# 780-00021_rev1_pg1_3-Chan_IR_Thermocoupl.net
KiCad netlist of a schematic drawn in Altium Designer
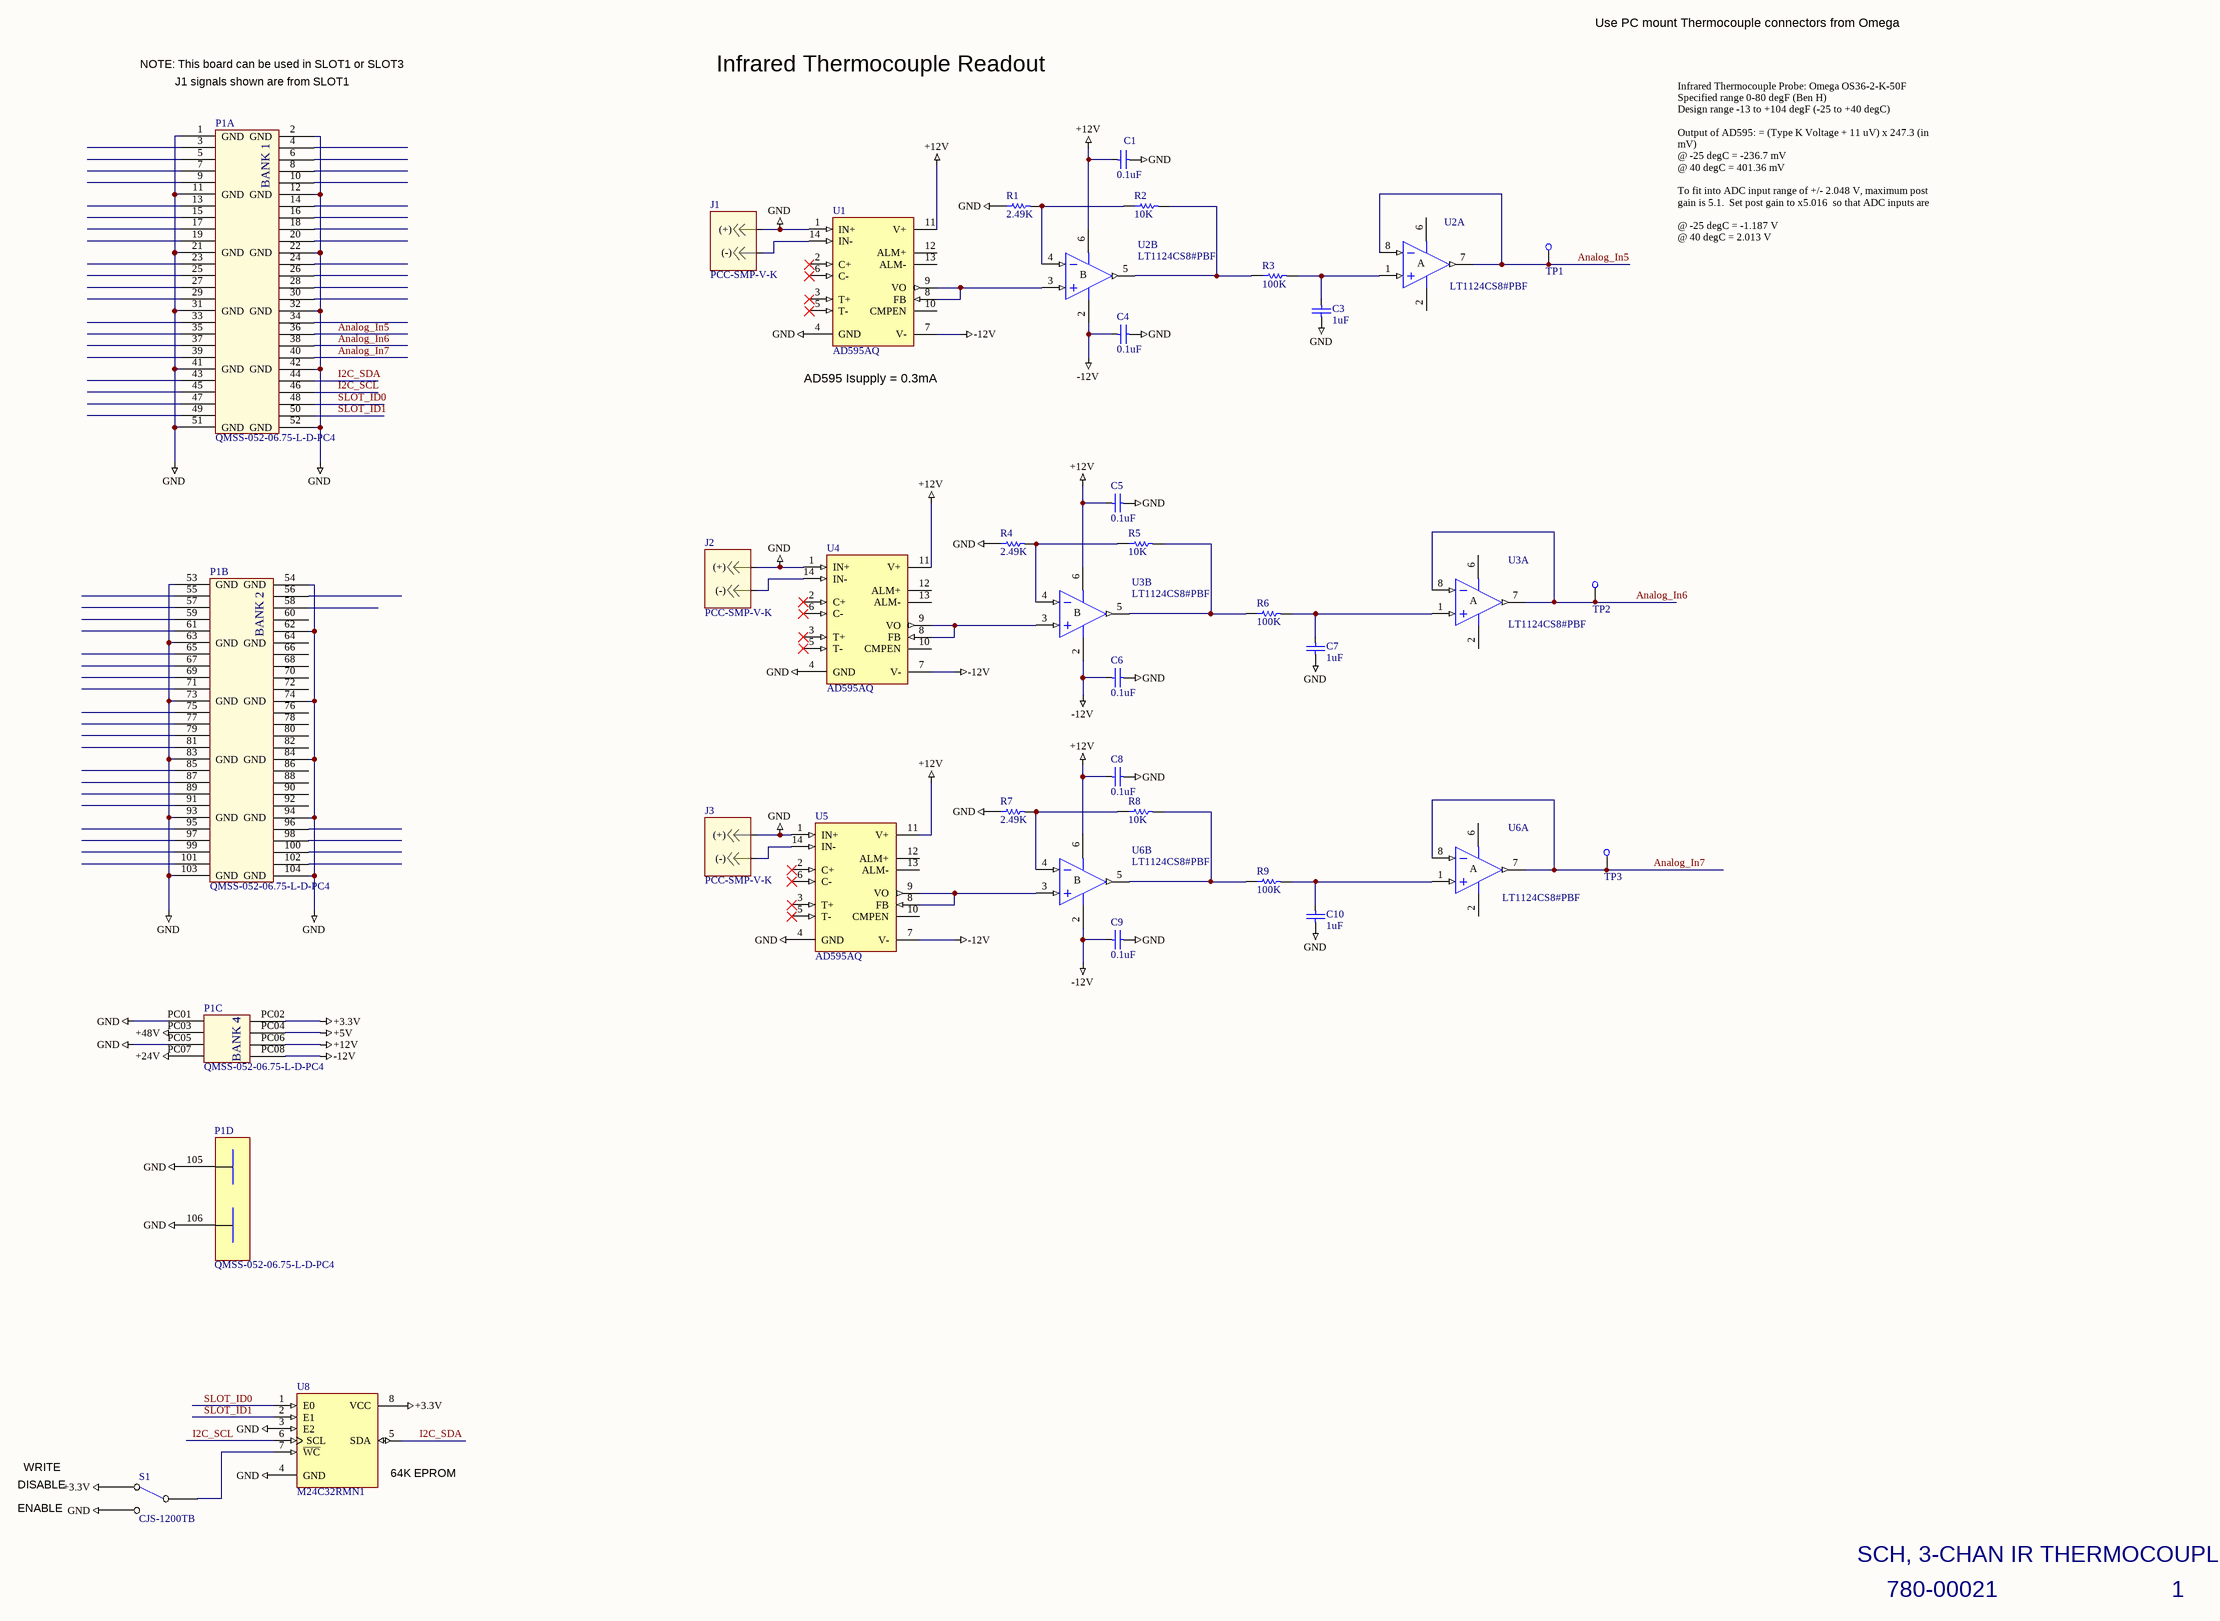
[diagram p0: 780-00021_rev1,pg1,3-Chan IR Thermocouple Apps Module.SchDoc]

(export (version "E")
  (design (tool "Eeschema 10.0.6"))
  (components
    (comp (ref "C1")
      (value "0.1uF")
      (footprint "SMD_0805")
      (description "Capacitor")
      (fields (field (name "Comment") "Cap SMD"))
      (libsource (lib "Richs Schematic Components") (part "Cap SMD"))
    )
    (comp (ref "C3")
      (value "1uF")
      (footprint "SMD_0805")
      (description "Capacitor")
      (fields (field (name "Comment") "Cap SMD"))
      (libsource (lib "Richs Schematic Components") (part "Cap SMD"))
    )
    (comp (ref "C4")
      (value "0.1uF")
      (footprint "SMD_0805")
      (description "Capacitor")
      (fields (field (name "Comment") "Cap SMD"))
      (libsource (lib "Richs Schematic Components") (part "Cap SMD"))
    )
    (comp (ref "C5")
      (value "0.1uF")
      (footprint "SMD_0805")
      (description "Capacitor")
      (fields (field (name "Comment") "Cap SMD"))
      (libsource (lib "Richs Schematic Components") (part "Cap SMD"))
    )
    (comp (ref "C6")
      (value "0.1uF")
      (footprint "SMD_0805")
      (description "Capacitor")
      (fields (field (name "Comment") "Cap SMD"))
      (libsource (lib "Richs Schematic Components") (part "Cap SMD"))
    )
    (comp (ref "C7")
      (value "1uF")
      (footprint "SMD_0805")
      (description "Capacitor")
      (fields (field (name "Comment") "Cap SMD"))
      (libsource (lib "Richs Schematic Components") (part "Cap SMD"))
    )
    (comp (ref "C8")
      (value "0.1uF")
      (footprint "SMD_0805")
      (description "Capacitor")
      (fields (field (name "Comment") "Cap SMD"))
      (libsource (lib "Richs Schematic Components") (part "Cap SMD"))
    )
    (comp (ref "C9")
      (value "0.1uF")
      (footprint "SMD_0805")
      (description "Capacitor")
      (fields (field (name "Comment") "Cap SMD"))
      (libsource (lib "Richs Schematic Components") (part "Cap SMD"))
    )
    (comp (ref "C10")
      (value "1uF")
      (footprint "SMD_0805")
      (description "Capacitor")
      (fields (field (name "Comment") "Cap SMD"))
      (libsource (lib "Richs Schematic Components") (part "Cap SMD"))
    )
    (comp (ref "J1")
      (value "PCC-SMP-V-K")
      (footprint "THERMOCOUPLE, Vertical")
      (description "T/C Conn PCB mount vertical")
      (libsource (lib "Richs Schematic Components") (part "Thermocouple Connector"))
    )
    (comp (ref "J2")
      (value "PCC-SMP-V-K")
      (footprint "THERMOCOUPLE, Vertical")
      (description "T/C Conn PCB mount vertical")
      (libsource (lib "Richs Schematic Components") (part "Thermocouple Connector"))
    )
    (comp (ref "J3")
      (value "PCC-SMP-V-K")
      (footprint "THERMOCOUPLE, Vertical")
      (description "T/C Conn PCB mount vertical")
      (libsource (lib "Richs Schematic Components") (part "Thermocouple Connector"))
    )
    (comp (ref "P1")
      (value "QMSS-052-06.75-L-D-PC4")
      (footprint "QMS SMD PWR PINS - 104PIN")
      (description "SAMTEC QMSS W/PWR PINS")
      (fields (field (name "MANUFACTURER") "SAMTEC"))
      (libsource (lib "Richs Schematic Components") (part "QMSS-PC4-104 pin"))
    )
    (comp (ref "R1")
      (value "2.49K")
      (footprint "SMD_0805")
      (description "Resistor 0805")
      (fields (field (name "MANUFACTURER") "Vishay/Dale") (field (name "Comment") "Res 0805"))
      (libsource (lib "Richs Schematic Components") (part "Res SMD"))
    )
    (comp (ref "R2")
      (value "10K")
      (footprint "SMD_0805")
      (description "Resistor 0805")
      (fields (field (name "MANUFACTURER") "Vishay/Dale") (field (name "Comment") "Res 0805"))
      (libsource (lib "Richs Schematic Components") (part "Res SMD"))
    )
    (comp (ref "R3")
      (value "100K")
      (footprint "SMD_0805")
      (description "Resistor 0805")
      (fields (field (name "MANUFACTURER") "Vishay/Dale") (field (name "Comment") "Res 0805"))
      (libsource (lib "Richs Schematic Components") (part "Res SMD"))
    )
    (comp (ref "R4")
      (value "2.49K")
      (footprint "SMD_0805")
      (description "Resistor 0805")
      (fields (field (name "MANUFACTURER") "Vishay/Dale") (field (name "Comment") "Res 0805"))
      (libsource (lib "Richs Schematic Components") (part "Res SMD"))
    )
    (comp (ref "R5")
      (value "10K")
      (footprint "SMD_0805")
      (description "Resistor 0805")
      (fields (field (name "MANUFACTURER") "Vishay/Dale") (field (name "Comment") "Res 0805"))
      (libsource (lib "Richs Schematic Components") (part "Res SMD"))
    )
    (comp (ref "R6")
      (value "100K")
      (footprint "SMD_0805")
      (description "Resistor 0805")
      (fields (field (name "MANUFACTURER") "Vishay/Dale") (field (name "Comment") "Res 0805"))
      (libsource (lib "Richs Schematic Components") (part "Res SMD"))
    )
    (comp (ref "R7")
      (value "2.49K")
      (footprint "SMD_0805")
      (description "Resistor 0805")
      (fields (field (name "MANUFACTURER") "Vishay/Dale") (field (name "Comment") "Res 0805"))
      (libsource (lib "Richs Schematic Components") (part "Res SMD"))
    )
    (comp (ref "R8")
      (value "10K")
      (footprint "SMD_0805")
      (description "Resistor 0805")
      (fields (field (name "MANUFACTURER") "Vishay/Dale") (field (name "Comment") "Res 0805"))
      (libsource (lib "Richs Schematic Components") (part "Res SMD"))
    )
    (comp (ref "R9")
      (value "100K")
      (footprint "SMD_0805")
      (description "Resistor 0805")
      (fields (field (name "MANUFACTURER") "Vishay/Dale") (field (name "Comment") "Res 0805"))
      (libsource (lib "Richs Schematic Components") (part "Res SMD"))
    )
    (comp (ref "S1")
      (value "CJS-1200TB")
      (footprint "CAS-120B")
      (fields (field (name "MANUFACTURER") "Copal Electronics"))
      (libsource (lib "JON_1_Library") (part "SW_SPDT_DOUG"))
    )
    (comp (ref "TP1")
      (value "Test Point SMD")
      (footprint "SMD_TEST POINT")
      (description "SMD loop test point")
      (libsource (lib "Richs Schematic Components") (part "Test Point SMD"))
    )
    (comp (ref "TP2")
      (value "Test Point SMD")
      (footprint "SMD_TEST POINT")
      (description "SMD loop test point")
      (libsource (lib "Richs Schematic Components") (part "Test Point SMD"))
    )
    (comp (ref "TP3")
      (value "Test Point SMD")
      (footprint "SMD_TEST POINT")
      (description "SMD loop test point")
      (libsource (lib "Richs Schematic Components") (part "Test Point SMD"))
    )
    (comp (ref "U1")
      (value "AD595AQ")
      (footprint "Q-14_A")
      (description "Monolithic Thermocouple Amplifier with Cold Junction Compensation")
      (fields (field (name "MANUFACTURER") "Analog Devices"))
      (libsource (lib "AD Thermocouple Amplifier") (part "AD595AQ"))
    )
    (comp (ref "U2")
      (value "LT1124CS8#PBF")
      (footprint "S8_N")
      (description "Dual Low Noise, High-Speed Precision Operational Amplifier")
      (libsource (lib "LT Operational Amplifier") (part "LT1124CS8#PBF"))
    )
    (comp (ref "U3")
      (value "LT1124CS8#PBF")
      (footprint "S8_N")
      (description "Dual Low Noise, High-Speed Precision Operational Amplifier")
      (libsource (lib "LT Operational Amplifier") (part "LT1124CS8#PBF"))
    )
    (comp (ref "U4")
      (value "AD595AQ")
      (footprint "Q-14_A")
      (description "Monolithic Thermocouple Amplifier with Cold Junction Compensation")
      (fields (field (name "MANUFACTURER") "Analog Devices"))
      (libsource (lib "AD Thermocouple Amplifier") (part "AD595AQ"))
    )
    (comp (ref "U5")
      (value "AD595AQ")
      (footprint "Q-14_A")
      (description "Monolithic Thermocouple Amplifier with Cold Junction Compensation")
      (fields (field (name "MANUFACTURER") "Analog Devices"))
      (libsource (lib "AD Thermocouple Amplifier") (part "AD595AQ"))
    )
    (comp (ref "U6")
      (value "LT1124CS8#PBF")
      (footprint "S8_N")
      (description "Dual Low Noise, High-Speed Precision Operational Amplifier")
      (libsource (lib "LT Operational Amplifier") (part "LT1124CS8#PBF"))
    )
    (comp (ref "U8")
      (value "M24C32RMN1")
      (footprint "SOP8_N")
      (description "32 Kbit Serial I²C Bus EEPROM")
      (libsource (lib "ST Memory EEPROM Serial") (part "M24C32RMN1"))
    )
  )
  (nets
    (net (code "1") (name "+3.3V") (class "Default")
      (node (ref "P1") (pin "PC02") (pinfunction "PC02_PC02") (pintype "passive"))
      (node (ref "S1") (pin "3") (pinfunction "NC_3") (pintype "passive"))
      (node (ref "U8") (pin "8") (pinfunction "VCC_8") (pintype "power_in"))
    )
    (net (code "2") (name "+5V") (class "Default")
      (node (ref "P1") (pin "PC04") (pinfunction "PC04_PC04") (pintype "passive"))
    )
    (net (code "3") (name "+12V") (class "Default")
      (node (ref "C1") (pin "2") (pinfunction "2_2") (pintype "passive"))
      (node (ref "C5") (pin "2") (pinfunction "2_2") (pintype "passive"))
      (node (ref "C8") (pin "2") (pinfunction "2_2") (pintype "passive"))
      (node (ref "P1") (pin "PC06") (pinfunction "PC06_PC06") (pintype "passive"))
      (node (ref "U1") (pin "11") (pinfunction "V+_11") (pintype "power_in"))
      (node (ref "U2") (pin "6") (pinfunction "V+_6") (pintype "power_in"))
      (node (ref "U3") (pin "6") (pinfunction "V+_6") (pintype "power_in"))
      (node (ref "U4") (pin "11") (pinfunction "V+_11") (pintype "power_in"))
      (node (ref "U5") (pin "11") (pinfunction "V+_11") (pintype "power_in"))
      (node (ref "U6") (pin "6") (pinfunction "V+_6") (pintype "power_in"))
    )
    (net (code "6") (name "-12V") (class "Default")
      (node (ref "C4") (pin "2") (pinfunction "2_2") (pintype "passive"))
      (node (ref "C6") (pin "2") (pinfunction "2_2") (pintype "passive"))
      (node (ref "C9") (pin "2") (pinfunction "2_2") (pintype "passive"))
      (node (ref "P1") (pin "PC08") (pinfunction "PC08_PC08") (pintype "passive"))
      (node (ref "U1") (pin "7") (pinfunction "V-_7") (pintype "power_in"))
      (node (ref "U2") (pin "2") (pinfunction "V-_2") (pintype "power_in"))
      (node (ref "U3") (pin "2") (pinfunction "V-_2") (pintype "power_in"))
      (node (ref "U4") (pin "7") (pinfunction "V-_7") (pintype "power_in"))
      (node (ref "U5") (pin "7") (pinfunction "V-_7") (pintype "power_in"))
      (node (ref "U6") (pin "2") (pinfunction "V-_2") (pintype "power_in"))
    )
    (net (code "7") (name "/Analog_In5") (class "Default")
      (node (ref "P1") (pin "36") (pinfunction "36_36") (pintype "passive"))
      (node (ref "TP1") (pin "1") (pinfunction "TP_1") (pintype "passive"))
      (node (ref "U2") (pin "7") (pinfunction "OUT_7") (pintype "output"))
      (node (ref "U2") (pin "8") (pinfunction "IN-_8") (pintype "input"))
    )
    (net (code "8") (name "/Analog_In6") (class "Default")
      (node (ref "P1") (pin "38") (pinfunction "38_38") (pintype "passive"))
      (node (ref "TP2") (pin "1") (pinfunction "TP_1") (pintype "passive"))
      (node (ref "U3") (pin "7") (pinfunction "OUT_7") (pintype "output"))
      (node (ref "U3") (pin "8") (pinfunction "IN-_8") (pintype "input"))
    )
    (net (code "9") (name "/Analog_In7") (class "Default")
      (node (ref "P1") (pin "40") (pinfunction "40_40") (pintype "passive"))
      (node (ref "TP3") (pin "1") (pinfunction "TP_1") (pintype "passive"))
      (node (ref "U6") (pin "7") (pinfunction "OUT_7") (pintype "output"))
      (node (ref "U6") (pin "8") (pinfunction "IN-_8") (pintype "input"))
    )
    (net (code "10") (name "/I2C_SCL") (class "Default")
      (node (ref "P1") (pin "46") (pinfunction "46_46") (pintype "passive"))
      (node (ref "U8") (pin "6") (pinfunction "SCL_6") (pintype "input"))
    )
    (net (code "11") (name "/I2C_SDA") (class "Default")
      (node (ref "P1") (pin "44") (pinfunction "44_44") (pintype "passive"))
      (node (ref "U8") (pin "5") (pinfunction "SDA_5") (pintype "bidirectional"))
    )
    (net (code "12") (name "/SLOT_ID0") (class "Default")
      (node (ref "P1") (pin "48") (pinfunction "48_48") (pintype "passive"))
      (node (ref "U8") (pin "1") (pinfunction "E0_1") (pintype "input"))
    )
    (net (code "13") (name "/SLOT_ID1") (class "Default")
      (node (ref "P1") (pin "50") (pinfunction "50_50") (pintype "passive"))
      (node (ref "U8") (pin "2") (pinfunction "E1_2") (pintype "input"))
    )
    (net (code "14") (name "GND") (class "Default")
      (node (ref "C1") (pin "1") (pinfunction "1_1") (pintype "passive"))
      (node (ref "C10") (pin "1") (pinfunction "1_1") (pintype "passive"))
      (node (ref "C3") (pin "1") (pinfunction "1_1") (pintype "passive"))
      (node (ref "C4") (pin "1") (pinfunction "1_1") (pintype "passive"))
      (node (ref "C5") (pin "1") (pinfunction "1_1") (pintype "passive"))
      (node (ref "C6") (pin "1") (pinfunction "1_1") (pintype "passive"))
      (node (ref "C7") (pin "1") (pinfunction "1_1") (pintype "passive"))
      (node (ref "C8") (pin "1") (pinfunction "1_1") (pintype "passive"))
      (node (ref "C9") (pin "1") (pinfunction "1_1") (pintype "passive"))
      (node (ref "J1") (pin "1") (pinfunction "(+)_1") (pintype "passive"))
      (node (ref "J2") (pin "1") (pinfunction "(+)_1") (pintype "passive"))
      (node (ref "J3") (pin "1") (pinfunction "(+)_1") (pintype "passive"))
      (node (ref "P1") (pin "1") (pinfunction "GND_1") (pintype "passive"))
      (node (ref "P1") (pin "103") (pinfunction "GND_103") (pintype "passive"))
      (node (ref "P1") (pin "104") (pinfunction "GND_104") (pintype "passive"))
      (node (ref "P1") (pin "105") (pinfunction "GND_105") (pintype "passive"))
      (node (ref "P1") (pin "106") (pinfunction "GND_106") (pintype "passive"))
      (node (ref "P1") (pin "11") (pinfunction "GND_11") (pintype "passive"))
      (node (ref "P1") (pin "12") (pinfunction "GND_12") (pintype "passive"))
      (node (ref "P1") (pin "2") (pinfunction "GND_2") (pintype "passive"))
      (node (ref "P1") (pin "21") (pinfunction "GND_21") (pintype "passive"))
      (node (ref "P1") (pin "22") (pinfunction "GND_22") (pintype "passive"))
      (node (ref "P1") (pin "31") (pinfunction "GND_31") (pintype "passive"))
      (node (ref "P1") (pin "32") (pinfunction "GND_32") (pintype "passive"))
      (node (ref "P1") (pin "41") (pinfunction "GND_41") (pintype "passive"))
      (node (ref "P1") (pin "42") (pinfunction "GND_42") (pintype "passive"))
      (node (ref "P1") (pin "51") (pinfunction "GND_51") (pintype "passive"))
      (node (ref "P1") (pin "52") (pinfunction "GND_52") (pintype "passive"))
      (node (ref "P1") (pin "53") (pinfunction "GND_53") (pintype "passive"))
      (node (ref "P1") (pin "54") (pinfunction "GND_54") (pintype "passive"))
      (node (ref "P1") (pin "62") (pinfunction "62_62") (pintype "passive"))
      (node (ref "P1") (pin "63") (pinfunction "GND_63") (pintype "passive"))
      (node (ref "P1") (pin "73") (pinfunction "GND_73") (pintype "passive"))
      (node (ref "P1") (pin "74") (pinfunction "GND_74") (pintype "passive"))
      (node (ref "P1") (pin "83") (pinfunction "GND_83") (pintype "passive"))
      (node (ref "P1") (pin "84") (pinfunction "GND_84") (pintype "passive"))
      (node (ref "P1") (pin "93") (pinfunction "GND_93") (pintype "passive"))
      (node (ref "P1") (pin "94") (pinfunction "GND_94") (pintype "passive"))
      (node (ref "P1") (pin "PC01") (pinfunction "PC01_PC01") (pintype "passive"))
      (node (ref "P1") (pin "PC05") (pinfunction "PC05_PC05") (pintype "passive"))
      (node (ref "R1") (pin "1") (pinfunction "1_1") (pintype "passive"))
      (node (ref "R4") (pin "1") (pinfunction "1_1") (pintype "passive"))
      (node (ref "R7") (pin "1") (pinfunction "1_1") (pintype "passive"))
      (node (ref "S1") (pin "1") (pinfunction "NO_1") (pintype "passive"))
      (node (ref "U1") (pin "1") (pinfunction "IN+_1") (pintype "input"))
      (node (ref "U1") (pin "4") (pinfunction "GND_4") (pintype "power_in"))
      (node (ref "U4") (pin "1") (pinfunction "IN+_1") (pintype "input"))
      (node (ref "U4") (pin "4") (pinfunction "GND_4") (pintype "power_in"))
      (node (ref "U5") (pin "1") (pinfunction "IN+_1") (pintype "input"))
      (node (ref "U5") (pin "4") (pinfunction "GND_4") (pintype "power_in"))
      (node (ref "U8") (pin "3") (pinfunction "E2_3") (pintype "input"))
      (node (ref "U8") (pin "4") (pinfunction "GND_4") (pintype "power_in"))
    )
    (net (code "15") (name "Net-(J1-(-))") (class "Default")
      (node (ref "J1") (pin "2") (pinfunction "(-)_2") (pintype "passive"))
      (node (ref "U1") (pin "14") (pinfunction "IN-_14") (pintype "input"))
    )
    (net (code "16") (name "Net-(J2-(-))") (class "Default")
      (node (ref "J2") (pin "2") (pinfunction "(-)_2") (pintype "passive"))
      (node (ref "U4") (pin "14") (pinfunction "IN-_14") (pintype "input"))
    )
    (net (code "17") (name "Net-(J3-(-))") (class "Default")
      (node (ref "J3") (pin "2") (pinfunction "(-)_2") (pintype "passive"))
      (node (ref "U5") (pin "14") (pinfunction "IN-_14") (pintype "input"))
    )
    (net (code "18") (name "Net-(S1-COM)") (class "Default")
      (node (ref "S1") (pin "2") (pinfunction "COM_2") (pintype "passive"))
      (node (ref "U8") (pin "7") (pinfunction "~{WC}_7") (pintype "input"))
    )
    (net (code "19") (name "Net-(U1-FB)") (class "Default")
      (node (ref "U1") (pin "8") (pinfunction "FB_8") (pintype "input"))
      (node (ref "U1") (pin "9") (pinfunction "VO_9") (pintype "output"))
      (node (ref "U2") (pin "3") (pinfunction "IN+_3") (pintype "input"))
    )
    (net (code "20") (name "Net-(U2A-IN+)") (class "Default")
      (node (ref "C3") (pin "2") (pinfunction "2_2") (pintype "passive"))
      (node (ref "R3") (pin "2") (pinfunction "2_2") (pintype "passive"))
      (node (ref "U2") (pin "1") (pinfunction "IN+_1") (pintype "input"))
    )
    (net (code "21") (name "Net-(U2B-IN-)") (class "Default")
      (node (ref "R1") (pin "2") (pinfunction "2_2") (pintype "passive"))
      (node (ref "R2") (pin "1") (pinfunction "1_1") (pintype "passive"))
      (node (ref "U2") (pin "4") (pinfunction "IN-_4") (pintype "input"))
    )
    (net (code "22") (name "Net-(U2B-OUT)") (class "Default")
      (node (ref "R2") (pin "2") (pinfunction "2_2") (pintype "passive"))
      (node (ref "R3") (pin "1") (pinfunction "1_1") (pintype "passive"))
      (node (ref "U2") (pin "5") (pinfunction "OUT_5") (pintype "output"))
    )
    (net (code "23") (name "Net-(U3A-IN+)") (class "Default")
      (node (ref "C7") (pin "2") (pinfunction "2_2") (pintype "passive"))
      (node (ref "R6") (pin "2") (pinfunction "2_2") (pintype "passive"))
      (node (ref "U3") (pin "1") (pinfunction "IN+_1") (pintype "input"))
    )
    (net (code "24") (name "Net-(U3B-IN+)") (class "Default")
      (node (ref "U3") (pin "3") (pinfunction "IN+_3") (pintype "input"))
      (node (ref "U4") (pin "8") (pinfunction "FB_8") (pintype "input"))
      (node (ref "U4") (pin "9") (pinfunction "VO_9") (pintype "output"))
    )
    (net (code "25") (name "Net-(U3B-IN-)") (class "Default")
      (node (ref "R4") (pin "2") (pinfunction "2_2") (pintype "passive"))
      (node (ref "R5") (pin "1") (pinfunction "1_1") (pintype "passive"))
      (node (ref "U3") (pin "4") (pinfunction "IN-_4") (pintype "input"))
    )
    (net (code "26") (name "Net-(U3B-OUT)") (class "Default")
      (node (ref "R5") (pin "2") (pinfunction "2_2") (pintype "passive"))
      (node (ref "R6") (pin "1") (pinfunction "1_1") (pintype "passive"))
      (node (ref "U3") (pin "5") (pinfunction "OUT_5") (pintype "output"))
    )
    (net (code "27") (name "Net-(U5-FB)") (class "Default")
      (node (ref "U5") (pin "8") (pinfunction "FB_8") (pintype "input"))
      (node (ref "U5") (pin "9") (pinfunction "VO_9") (pintype "output"))
      (node (ref "U6") (pin "3") (pinfunction "IN+_3") (pintype "input"))
    )
    (net (code "28") (name "Net-(U6A-IN+)") (class "Default")
      (node (ref "C10") (pin "2") (pinfunction "2_2") (pintype "passive"))
      (node (ref "R9") (pin "2") (pinfunction "2_2") (pintype "passive"))
      (node (ref "U6") (pin "1") (pinfunction "IN+_1") (pintype "input"))
    )
    (net (code "29") (name "Net-(U6B-IN-)") (class "Default")
      (node (ref "R7") (pin "2") (pinfunction "2_2") (pintype "passive"))
      (node (ref "R8") (pin "1") (pinfunction "1_1") (pintype "passive"))
      (node (ref "U6") (pin "4") (pinfunction "IN-_4") (pintype "input"))
    )
    (net (code "30") (name "Net-(U6B-OUT)") (class "Default")
      (node (ref "R8") (pin "2") (pinfunction "2_2") (pintype "passive"))
      (node (ref "R9") (pin "1") (pinfunction "1_1") (pintype "passive"))
      (node (ref "U6") (pin "5") (pinfunction "OUT_5") (pintype "output"))
    )
    (net (code "31") (name "unconnected-(P1-Pad3)") (class "Default")
      (node (ref "P1") (pin "3") (pinfunction "3_3") (pintype "passive"))
    )
    (net (code "32") (name "unconnected-(P1-Pad4)") (class "Default")
      (node (ref "P1") (pin "4") (pinfunction "4_4") (pintype "passive"))
    )
    (net (code "33") (name "unconnected-(P1-Pad5)") (class "Default")
      (node (ref "P1") (pin "5") (pinfunction "5_5") (pintype "passive"))
    )
    (net (code "34") (name "unconnected-(P1-Pad6)") (class "Default")
      (node (ref "P1") (pin "6") (pinfunction "6_6") (pintype "passive"))
    )
    (net (code "35") (name "unconnected-(P1-Pad7)") (class "Default")
      (node (ref "P1") (pin "7") (pinfunction "7_7") (pintype "passive"))
    )
    (net (code "36") (name "unconnected-(P1-Pad8)") (class "Default")
      (node (ref "P1") (pin "8") (pinfunction "8_8") (pintype "passive"))
    )
    (net (code "37") (name "unconnected-(P1-Pad9)") (class "Default")
      (node (ref "P1") (pin "9") (pinfunction "9_9") (pintype "passive"))
    )
    (net (code "38") (name "unconnected-(P1-Pad10)") (class "Default")
      (node (ref "P1") (pin "10") (pinfunction "10_10") (pintype "passive"))
    )
    (net (code "39") (name "unconnected-(P1-Pad13)") (class "Default")
      (node (ref "P1") (pin "13") (pinfunction "13_13") (pintype "passive"))
    )
    (net (code "40") (name "unconnected-(P1-Pad14)") (class "Default")
      (node (ref "P1") (pin "14") (pinfunction "14_14") (pintype "passive"))
    )
    (net (code "41") (name "unconnected-(P1-Pad15)") (class "Default")
      (node (ref "P1") (pin "15") (pinfunction "15_15") (pintype "passive"))
    )
    (net (code "42") (name "unconnected-(P1-Pad16)") (class "Default")
      (node (ref "P1") (pin "16") (pinfunction "16_16") (pintype "passive"))
    )
    (net (code "43") (name "unconnected-(P1-Pad17)") (class "Default")
      (node (ref "P1") (pin "17") (pinfunction "17_17") (pintype "passive"))
    )
    (net (code "44") (name "unconnected-(P1-Pad18)") (class "Default")
      (node (ref "P1") (pin "18") (pinfunction "18_18") (pintype "passive"))
    )
    (net (code "45") (name "unconnected-(P1-Pad19)") (class "Default")
      (node (ref "P1") (pin "19") (pinfunction "19_19") (pintype "passive"))
    )
    (net (code "46") (name "unconnected-(P1-Pad20)") (class "Default")
      (node (ref "P1") (pin "20") (pinfunction "20_20") (pintype "passive"))
    )
    (net (code "47") (name "unconnected-(P1-Pad23)") (class "Default")
      (node (ref "P1") (pin "23") (pinfunction "23_23") (pintype "passive"))
    )
    (net (code "48") (name "unconnected-(P1-Pad24)") (class "Default")
      (node (ref "P1") (pin "24") (pinfunction "24_24") (pintype "passive"))
    )
    (net (code "49") (name "unconnected-(P1-Pad25)") (class "Default")
      (node (ref "P1") (pin "25") (pinfunction "25_25") (pintype "passive"))
    )
    (net (code "50") (name "unconnected-(P1-Pad26)") (class "Default")
      (node (ref "P1") (pin "26") (pinfunction "26_26") (pintype "passive"))
    )
    (net (code "51") (name "unconnected-(P1-Pad27)") (class "Default")
      (node (ref "P1") (pin "27") (pinfunction "27_27") (pintype "passive"))
    )
    (net (code "52") (name "unconnected-(P1-Pad28)") (class "Default")
      (node (ref "P1") (pin "28") (pinfunction "28_28") (pintype "passive"))
    )
    (net (code "53") (name "unconnected-(P1-Pad29)") (class "Default")
      (node (ref "P1") (pin "29") (pinfunction "29_29") (pintype "passive"))
    )
    (net (code "54") (name "unconnected-(P1-Pad30)") (class "Default")
      (node (ref "P1") (pin "30") (pinfunction "30_30") (pintype "passive"))
    )
    (net (code "55") (name "unconnected-(P1-Pad33)") (class "Default")
      (node (ref "P1") (pin "33") (pinfunction "33_33") (pintype "passive"))
    )
    (net (code "56") (name "unconnected-(P1-Pad34)") (class "Default")
      (node (ref "P1") (pin "34") (pinfunction "34_34") (pintype "passive"))
    )
    (net (code "57") (name "unconnected-(P1-Pad35)") (class "Default")
      (node (ref "P1") (pin "35") (pinfunction "35_35") (pintype "passive"))
    )
    (net (code "58") (name "unconnected-(P1-Pad37)") (class "Default")
      (node (ref "P1") (pin "37") (pinfunction "37_37") (pintype "passive"))
    )
    (net (code "59") (name "unconnected-(P1-Pad39)") (class "Default")
      (node (ref "P1") (pin "39") (pinfunction "39_39") (pintype "passive"))
    )
    (net (code "60") (name "unconnected-(P1-Pad43)") (class "Default")
      (node (ref "P1") (pin "43") (pinfunction "43_43") (pintype "passive"))
    )
    (net (code "61") (name "unconnected-(P1-Pad45)") (class "Default")
      (node (ref "P1") (pin "45") (pinfunction "45_45") (pintype "passive"))
    )
    (net (code "62") (name "unconnected-(P1-Pad47)") (class "Default")
      (node (ref "P1") (pin "47") (pinfunction "47_47") (pintype "passive"))
    )
    (net (code "63") (name "unconnected-(P1-Pad49)") (class "Default")
      (node (ref "P1") (pin "49") (pinfunction "49_49") (pintype "passive"))
    )
    (net (code "64") (name "unconnected-(P1-Pad55)") (class "Default")
      (node (ref "P1") (pin "55") (pinfunction "55_55") (pintype "passive"))
    )
    (net (code "65") (name "unconnected-(P1-Pad56)") (class "Default")
      (node (ref "P1") (pin "56") (pinfunction "56_56") (pintype "passive"))
    )
    (net (code "66") (name "unconnected-(P1-Pad57)") (class "Default")
      (node (ref "P1") (pin "57") (pinfunction "57_57") (pintype "passive"))
    )
    (net (code "67") (name "unconnected-(P1-Pad58)") (class "Default")
      (node (ref "P1") (pin "58") (pinfunction "58_58") (pintype "passive"))
    )
    (net (code "68") (name "unconnected-(P1-Pad59)") (class "Default")
      (node (ref "P1") (pin "59") (pinfunction "59_59") (pintype "passive"))
    )
    (net (code "69") (name "unconnected-(P1-Pad60)") (class "Default")
      (node (ref "P1") (pin "60") (pinfunction "60_60") (pintype "passive"))
    )
    (net (code "70") (name "unconnected-(P1-Pad61)") (class "Default")
      (node (ref "P1") (pin "61") (pinfunction "61_61") (pintype "passive"))
    )
    (net (code "71") (name "unconnected-(P1-Pad65)") (class "Default")
      (node (ref "P1") (pin "65") (pinfunction "65_65") (pintype "passive"))
    )
    (net (code "72") (name "unconnected-(P1-Pad66)") (class "Default")
      (node (ref "P1") (pin "66") (pinfunction "66_66") (pintype "passive"))
    )
    (net (code "73") (name "unconnected-(P1-Pad67)") (class "Default")
      (node (ref "P1") (pin "67") (pinfunction "67_67") (pintype "passive"))
    )
    (net (code "74") (name "unconnected-(P1-Pad68)") (class "Default")
      (node (ref "P1") (pin "68") (pinfunction "68_68") (pintype "passive"))
    )
    (net (code "75") (name "unconnected-(P1-Pad69)") (class "Default")
      (node (ref "P1") (pin "69") (pinfunction "69_69") (pintype "passive"))
    )
    (net (code "76") (name "unconnected-(P1-Pad70)") (class "Default")
      (node (ref "P1") (pin "70") (pinfunction "70_70") (pintype "passive"))
    )
    (net (code "77") (name "unconnected-(P1-Pad71)") (class "Default")
      (node (ref "P1") (pin "71") (pinfunction "71_71") (pintype "passive"))
    )
    (net (code "78") (name "unconnected-(P1-Pad72)") (class "Default")
      (node (ref "P1") (pin "72") (pinfunction "72_72") (pintype "passive"))
    )
    (net (code "79") (name "unconnected-(P1-Pad75)") (class "Default")
      (node (ref "P1") (pin "75") (pinfunction "75_75") (pintype "passive"))
    )
    (net (code "80") (name "unconnected-(P1-Pad76)") (class "Default")
      (node (ref "P1") (pin "76") (pinfunction "76_76") (pintype "passive"))
    )
    (net (code "81") (name "unconnected-(P1-Pad77)") (class "Default")
      (node (ref "P1") (pin "77") (pinfunction "77_77") (pintype "passive"))
    )
    (net (code "82") (name "unconnected-(P1-Pad78)") (class "Default")
      (node (ref "P1") (pin "78") (pinfunction "78_78") (pintype "passive"))
    )
    (net (code "83") (name "unconnected-(P1-Pad79)") (class "Default")
      (node (ref "P1") (pin "79") (pinfunction "79_79") (pintype "passive"))
    )
    (net (code "84") (name "unconnected-(P1-Pad80)") (class "Default")
      (node (ref "P1") (pin "80") (pinfunction "80_80") (pintype "passive"))
    )
    (net (code "85") (name "unconnected-(P1-Pad81)") (class "Default")
      (node (ref "P1") (pin "81") (pinfunction "81_81") (pintype "passive"))
    )
    (net (code "86") (name "unconnected-(P1-Pad82)") (class "Default")
      (node (ref "P1") (pin "82") (pinfunction "82_82") (pintype "passive"))
    )
    (net (code "87") (name "unconnected-(P1-Pad85)") (class "Default")
      (node (ref "P1") (pin "85") (pinfunction "85_85") (pintype "passive"))
    )
    (net (code "88") (name "unconnected-(P1-Pad86)") (class "Default")
      (node (ref "P1") (pin "86") (pinfunction "86_86") (pintype "passive"))
    )
    (net (code "89") (name "unconnected-(P1-Pad87)") (class "Default")
      (node (ref "P1") (pin "87") (pinfunction "87_87") (pintype "passive"))
    )
    (net (code "90") (name "unconnected-(P1-Pad88)") (class "Default")
      (node (ref "P1") (pin "88") (pinfunction "88_88") (pintype "passive"))
    )
    (net (code "91") (name "unconnected-(P1-Pad89)") (class "Default")
      (node (ref "P1") (pin "89") (pinfunction "89_89") (pintype "passive"))
    )
    (net (code "92") (name "unconnected-(P1-Pad90)") (class "Default")
      (node (ref "P1") (pin "90") (pinfunction "90_90") (pintype "passive"))
    )
    (net (code "93") (name "unconnected-(P1-Pad91)") (class "Default")
      (node (ref "P1") (pin "91") (pinfunction "91_91") (pintype "passive"))
    )
    (net (code "94") (name "unconnected-(P1-Pad92)") (class "Default")
      (node (ref "P1") (pin "92") (pinfunction "92_92") (pintype "passive"))
    )
    (net (code "95") (name "unconnected-(P1-Pad95)") (class "Default")
      (node (ref "P1") (pin "95") (pinfunction "95_95") (pintype "passive"))
    )
    (net (code "96") (name "unconnected-(P1-Pad96)") (class "Default")
      (node (ref "P1") (pin "96") (pinfunction "96_96") (pintype "passive"))
    )
    (net (code "97") (name "unconnected-(P1-Pad97)") (class "Default")
      (node (ref "P1") (pin "97") (pinfunction "97_97") (pintype "passive"))
    )
    (net (code "98") (name "unconnected-(P1-Pad98)") (class "Default")
      (node (ref "P1") (pin "98") (pinfunction "98_98") (pintype "passive"))
    )
    (net (code "99") (name "unconnected-(P1-Pad99)") (class "Default")
      (node (ref "P1") (pin "99") (pinfunction "99_99") (pintype "passive"))
    )
    (net (code "100") (name "unconnected-(P1-Pad100)") (class "Default")
      (node (ref "P1") (pin "100") (pinfunction "100_100") (pintype "passive"))
    )
    (net (code "101") (name "unconnected-(P1-Pad101)") (class "Default")
      (node (ref "P1") (pin "101") (pinfunction "101_101") (pintype "passive"))
    )
    (net (code "102") (name "unconnected-(P1-Pad102)") (class "Default")
      (node (ref "P1") (pin "102") (pinfunction "102_102") (pintype "passive"))
    )
    (net (code "103") (name "unconnected-(P1-PadPC03)") (class "Default")
      (node (ref "P1") (pin "PC03") (pinfunction "PC03_PC03") (pintype "passive"))
    )
    (net (code "104") (name "unconnected-(P1-PadPC07)") (class "Default")
      (node (ref "P1") (pin "PC07") (pinfunction "PC07_PC07") (pintype "passive"))
    )
    (net (code "105") (name "unconnected-(P1B-GND-Pad64)") (class "Default")
      (node (ref "P1") (pin "64") (pinfunction "GND_64") (pintype "passive"))
    )
    (net (code "106") (name "unconnected-(U1-ALM+-Pad12)") (class "Default")
      (node (ref "U1") (pin "12") (pinfunction "ALM+_12") (pintype "passive"))
    )
    (net (code "107") (name "unconnected-(U1-ALM--Pad13)") (class "Default")
      (node (ref "U1") (pin "13") (pinfunction "ALM-_13") (pintype "passive"))
    )
    (net (code "108") (name "unconnected-(U1-C+-Pad2)") (class "Default")
      (node (ref "U1") (pin "2") (pinfunction "C+_2") (pintype "input+no_connect"))
    )
    (net (code "109") (name "unconnected-(U1-C--Pad6)") (class "Default")
      (node (ref "U1") (pin "6") (pinfunction "C-_6") (pintype "input+no_connect"))
    )
    (net (code "110") (name "unconnected-(U1-CMPEN-Pad10)") (class "Default")
      (node (ref "U1") (pin "10") (pinfunction "CMPEN_10") (pintype "passive"))
    )
    (net (code "111") (name "unconnected-(U1-T+-Pad3)") (class "Default")
      (node (ref "U1") (pin "3") (pinfunction "T+_3") (pintype "input+no_connect"))
    )
    (net (code "112") (name "unconnected-(U1-T--Pad5)") (class "Default")
      (node (ref "U1") (pin "5") (pinfunction "T-_5") (pintype "input+no_connect"))
    )
    (net (code "113") (name "unconnected-(U2A-V+-Pad6)") (class "Default")
      (node (ref "U2") (pin "6") (pinfunction "V+_6") (pintype "power_in"))
    )
    (net (code "114") (name "unconnected-(U2A-V--Pad2)") (class "Default")
      (node (ref "U2") (pin "2") (pinfunction "V-_2") (pintype "power_in"))
    )
    (net (code "115") (name "unconnected-(U3A-V+-Pad6)") (class "Default")
      (node (ref "U3") (pin "6") (pinfunction "V+_6") (pintype "power_in"))
    )
    (net (code "116") (name "unconnected-(U3A-V--Pad2)") (class "Default")
      (node (ref "U3") (pin "2") (pinfunction "V-_2") (pintype "power_in"))
    )
    (net (code "117") (name "unconnected-(U4-ALM+-Pad12)") (class "Default")
      (node (ref "U4") (pin "12") (pinfunction "ALM+_12") (pintype "passive"))
    )
    (net (code "118") (name "unconnected-(U4-ALM--Pad13)") (class "Default")
      (node (ref "U4") (pin "13") (pinfunction "ALM-_13") (pintype "passive"))
    )
    (net (code "119") (name "unconnected-(U4-C+-Pad2)") (class "Default")
      (node (ref "U4") (pin "2") (pinfunction "C+_2") (pintype "input+no_connect"))
    )
    (net (code "120") (name "unconnected-(U4-C--Pad6)") (class "Default")
      (node (ref "U4") (pin "6") (pinfunction "C-_6") (pintype "input+no_connect"))
    )
    (net (code "121") (name "unconnected-(U4-CMPEN-Pad10)") (class "Default")
      (node (ref "U4") (pin "10") (pinfunction "CMPEN_10") (pintype "passive"))
    )
    (net (code "122") (name "unconnected-(U4-T+-Pad3)") (class "Default")
      (node (ref "U4") (pin "3") (pinfunction "T+_3") (pintype "input+no_connect"))
    )
    (net (code "123") (name "unconnected-(U4-T--Pad5)") (class "Default")
      (node (ref "U4") (pin "5") (pinfunction "T-_5") (pintype "input+no_connect"))
    )
    (net (code "124") (name "unconnected-(U5-ALM+-Pad12)") (class "Default")
      (node (ref "U5") (pin "12") (pinfunction "ALM+_12") (pintype "passive"))
    )
    (net (code "125") (name "unconnected-(U5-ALM--Pad13)") (class "Default")
      (node (ref "U5") (pin "13") (pinfunction "ALM-_13") (pintype "passive"))
    )
    (net (code "126") (name "unconnected-(U5-C+-Pad2)") (class "Default")
      (node (ref "U5") (pin "2") (pinfunction "C+_2") (pintype "input+no_connect"))
    )
    (net (code "127") (name "unconnected-(U5-C--Pad6)") (class "Default")
      (node (ref "U5") (pin "6") (pinfunction "C-_6") (pintype "input+no_connect"))
    )
    (net (code "128") (name "unconnected-(U5-CMPEN-Pad10)") (class "Default")
      (node (ref "U5") (pin "10") (pinfunction "CMPEN_10") (pintype "passive"))
    )
    (net (code "129") (name "unconnected-(U5-T+-Pad3)") (class "Default")
      (node (ref "U5") (pin "3") (pinfunction "T+_3") (pintype "input+no_connect"))
    )
    (net (code "130") (name "unconnected-(U5-T--Pad5)") (class "Default")
      (node (ref "U5") (pin "5") (pinfunction "T-_5") (pintype "input+no_connect"))
    )
    (net (code "131") (name "unconnected-(U6A-V+-Pad6)") (class "Default")
      (node (ref "U6") (pin "6") (pinfunction "V+_6") (pintype "power_in"))
    )
    (net (code "132") (name "unconnected-(U6A-V--Pad2)") (class "Default")
      (node (ref "U6") (pin "2") (pinfunction "V-_2") (pintype "power_in"))
    )
  )
)
